# Periferico.net
KiCad netlist of a schematic drawn in Altium Designer
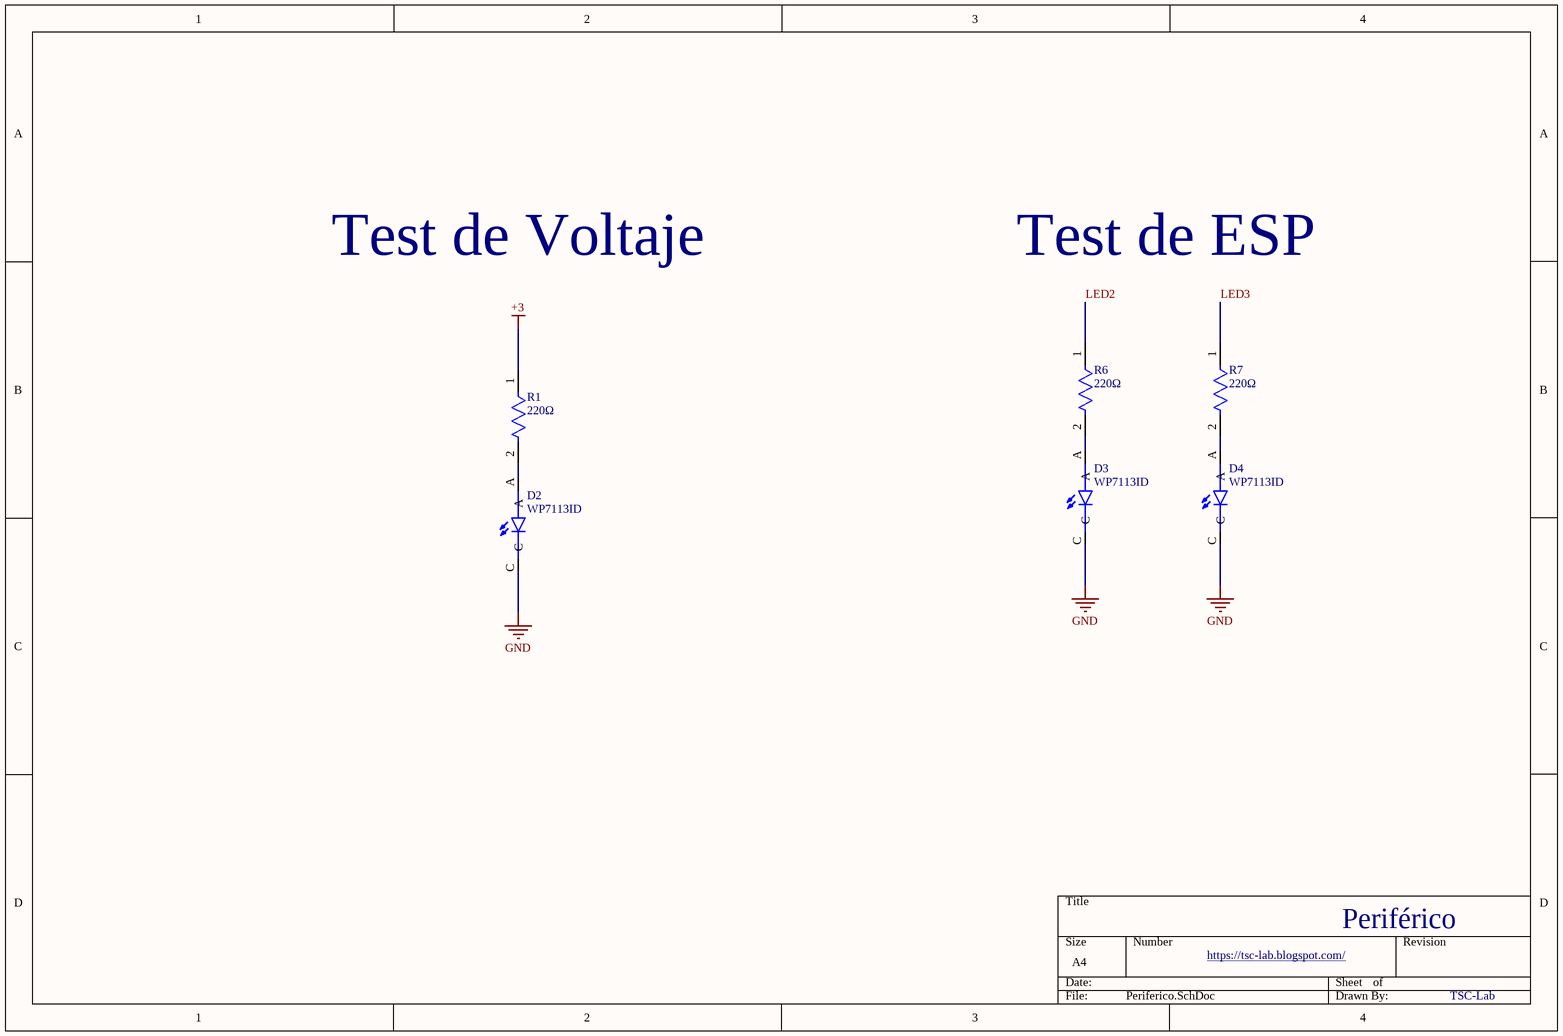
[diagram p0: Periferico.SchDoc]

(export (version "E")
  (design (tool "Eeschema 10.0.6"))
  (components
    (comp (ref "D2")
      (value "WP7113ID")
      (footprint "LED_WP7113ID")
      (description "LED; Thru-Hole; Green; T1-3/4; 5mm; Clear Lens; 25ma; 565nm; 200mcd; Round")
      (fields (field (name "MF") "{'manufacturer': u'Kingbright'}"))
      (libsource (lib "SnapEDA_Library") (part "WP7113ID"))
    )
    (comp (ref "D3")
      (value "WP7113ID")
      (footprint "LED_WP7113ID")
      (description "LED; Thru-Hole; Green; T1-3/4; 5mm; Clear Lens; 25ma; 565nm; 200mcd; Round")
      (fields (field (name "MF") "{'manufacturer': u'Kingbright'}"))
      (libsource (lib "SnapEDA_Library") (part "WP7113ID"))
    )
    (comp (ref "D4")
      (value "WP7113ID")
      (footprint "LED_WP7113ID")
      (description "LED; Thru-Hole; Green; T1-3/4; 5mm; Clear Lens; 25ma; 565nm; 200mcd; Round")
      (fields (field (name "MF") "{'manufacturer': u'Kingbright'}"))
      (libsource (lib "SnapEDA_Library") (part "WP7113ID"))
    )
    (comp (ref "R1")
      (value "Res_Vishay_SFR2500002200FR500_eec")
      (footprint "Vishay_SFR2500002200FR500_0")
      (description "RES 220 OHM 0.4W 1% AXIAL")
      (fields
        (field (name "PART NUMBER") "SFR2500002200FR500")
        (field (name "VOLTAGE") "250 V")
        (field (name "RESISTANCE") "220Ω")
      )
      (libsource (lib "SnapEDA_Library") (part "Res_Vishay_SFR2500002200FR500_eec"))
    )
    (comp (ref "R6")
      (value "Res_Vishay_SFR2500002200FR500_eec")
      (footprint "Vishay_SFR2500002200FR500_0")
      (description "RES 220 OHM 0.4W 1% AXIAL")
      (fields
        (field (name "PART NUMBER") "SFR2500002200FR500")
        (field (name "VOLTAGE") "250 V")
        (field (name "RESISTANCE") "220Ω")
      )
      (libsource (lib "SnapEDA_Library") (part "Res_Vishay_SFR2500002200FR500_eec"))
    )
    (comp (ref "R7")
      (value "Res_Vishay_SFR2500002200FR500_eec")
      (footprint "Vishay_SFR2500002200FR500_0")
      (description "RES 220 OHM 0.4W 1% AXIAL")
      (fields
        (field (name "PART NUMBER") "SFR2500002200FR500")
        (field (name "VOLTAGE") "250 V")
        (field (name "RESISTANCE") "220Ω")
      )
      (libsource (lib "SnapEDA_Library") (part "Res_Vishay_SFR2500002200FR500_eec"))
    )
  )
  (nets
    (net (code "1") (name "+3") (class "Default")
      (node (ref "R1") (pin "1") (pinfunction "1_1") (pintype "passive"))
    )
    (net (code "2") (name "/LED2") (class "Default")
      (node (ref "R6") (pin "1") (pinfunction "1_1") (pintype "passive"))
    )
    (net (code "3") (name "/LED3") (class "Default")
      (node (ref "R7") (pin "1") (pinfunction "1_1") (pintype "passive"))
    )
    (net (code "4") (name "GND") (class "Default")
      (node (ref "D2") (pin "C") (pinfunction "C_C") (pintype "passive"))
      (node (ref "D3") (pin "C") (pinfunction "C_C") (pintype "passive"))
      (node (ref "D4") (pin "C") (pinfunction "C_C") (pintype "passive"))
    )
    (net (code "5") (name "Net-(D2-PadA)") (class "Default")
      (node (ref "D2") (pin "A") (pinfunction "A_A") (pintype "passive"))
      (node (ref "R1") (pin "2") (pinfunction "2_2") (pintype "passive"))
    )
    (net (code "6") (name "Net-(D3-PadA)") (class "Default")
      (node (ref "D3") (pin "A") (pinfunction "A_A") (pintype "passive"))
      (node (ref "R6") (pin "2") (pinfunction "2_2") (pintype "passive"))
    )
    (net (code "7") (name "Net-(D4-PadA)") (class "Default")
      (node (ref "D4") (pin "A") (pinfunction "A_A") (pintype "passive"))
      (node (ref "R7") (pin "2") (pinfunction "2_2") (pintype "passive"))
    )
  )
)
